# LightSwitch4.net
KiCad netlist of a schematic drawn in EAGLE
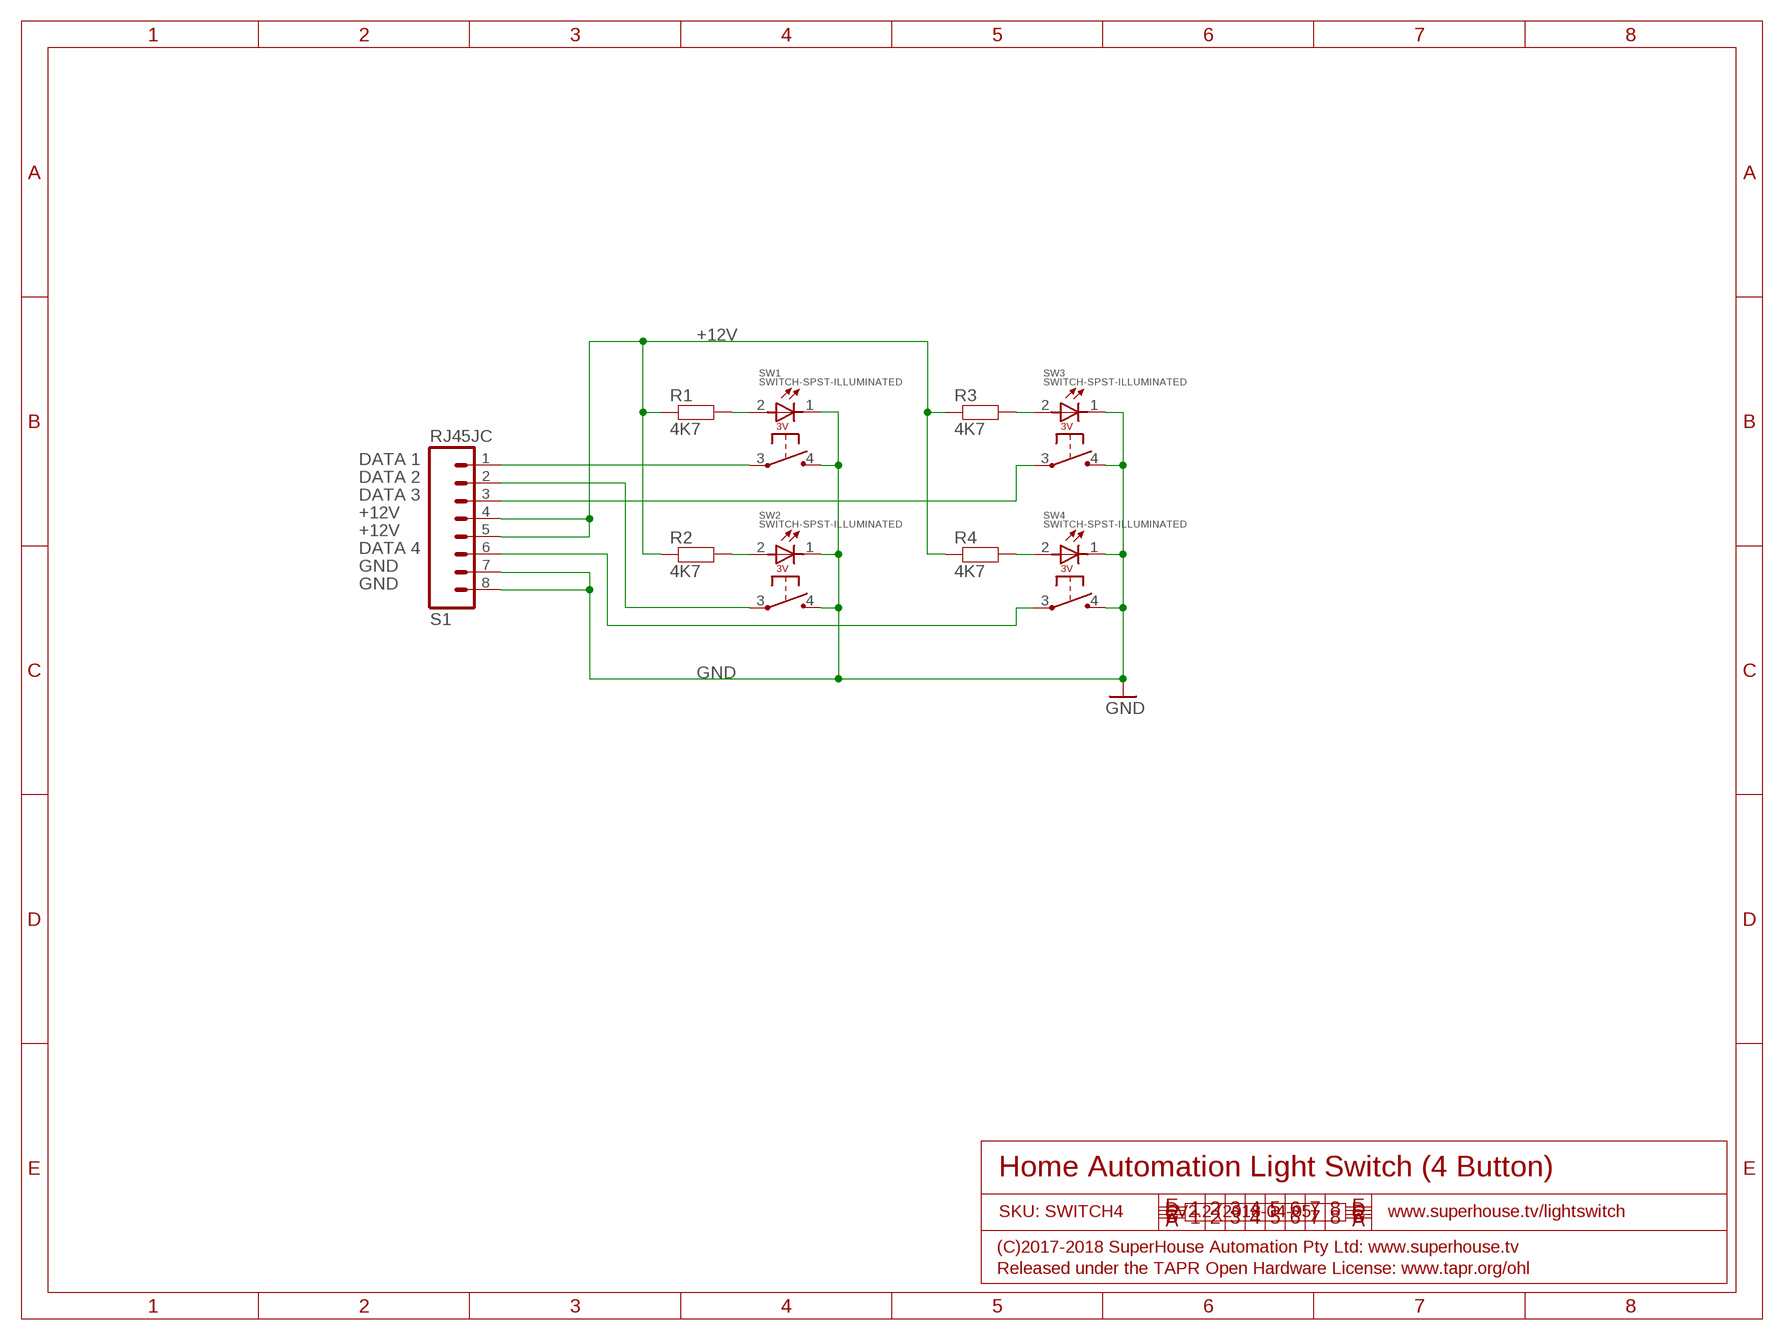
[diagram p0: schematic, sheet 1]

(export (version "E")
  (design (tool "Eeschema 10.0.6"))
  (components
    (comp (ref "R1")
      (value "4K7")
      (footprint "eagle-import:0603")
      (libsource (lib "eagle-import") (part "RESISTOR0603"))
    )
    (comp (ref "R2")
      (value "4K7")
      (footprint "eagle-import:0603")
      (libsource (lib "eagle-import") (part "RESISTOR0603"))
    )
    (comp (ref "R3")
      (value "4K7")
      (footprint "eagle-import:0603")
      (libsource (lib "eagle-import") (part "RESISTOR0603"))
    )
    (comp (ref "R4")
      (value "4K7")
      (footprint "eagle-import:0603")
      (libsource (lib "eagle-import") (part "RESISTOR0603"))
    )
    (comp (ref "S1")
      (value "RJ45JC")
      (footprint "eagle-import:RJ45")
      (libsource (lib "eagle-import") (part "RJ45JC"))
    )
    (comp (ref "SW1")
      (value "SWITCH-SPST-ILLUMINATED")
      (footprint "eagle-import:SWITCH-SPST-ILLUMINATED")
      (libsource (lib "eagle-import") (part "SWITCH-SPST-ILLUMINATED"))
    )
    (comp (ref "SW2")
      (value "SWITCH-SPST-ILLUMINATED")
      (footprint "eagle-import:SWITCH-SPST-ILLUMINATED")
      (libsource (lib "eagle-import") (part "SWITCH-SPST-ILLUMINATED"))
    )
    (comp (ref "SW3")
      (value "SWITCH-SPST-ILLUMINATED")
      (footprint "eagle-import:SWITCH-SPST-ILLUMINATED")
      (libsource (lib "eagle-import") (part "SWITCH-SPST-ILLUMINATED"))
    )
    (comp (ref "SW4")
      (value "SWITCH-SPST-ILLUMINATED")
      (footprint "eagle-import:SWITCH-SPST-ILLUMINATED")
      (libsource (lib "eagle-import") (part "SWITCH-SPST-ILLUMINATED"))
    )
  )
  (nets
    (net (code "1") (name "/+12V") (class "Default")
      (node (ref "R1") (pin "1") (pinfunction "1_1") (pintype "passive"))
      (node (ref "R2") (pin "1") (pinfunction "1_1") (pintype "passive"))
      (node (ref "R3") (pin "1") (pinfunction "1_1") (pintype "passive"))
      (node (ref "R4") (pin "1") (pinfunction "1_1") (pintype "passive"))
      (node (ref "S1") (pin "4") (pinfunction "4_4") (pintype "passive"))
      (node (ref "S1") (pin "5") (pinfunction "5_5") (pintype "passive"))
    )
    (net (code "2") (name "GND") (class "Default")
      (node (ref "S1") (pin "7") (pinfunction "7_7") (pintype "passive"))
      (node (ref "S1") (pin "8") (pinfunction "8_8") (pintype "passive"))
      (node (ref "SW1") (pin "1") (pinfunction "-_1") (pintype "passive"))
      (node (ref "SW1") (pin "4") (pinfunction "NO_4") (pintype "passive"))
      (node (ref "SW2") (pin "1") (pinfunction "-_1") (pintype "passive"))
      (node (ref "SW2") (pin "4") (pinfunction "NO_4") (pintype "passive"))
      (node (ref "SW3") (pin "1") (pinfunction "-_1") (pintype "passive"))
      (node (ref "SW3") (pin "4") (pinfunction "NO_4") (pintype "passive"))
      (node (ref "SW4") (pin "1") (pinfunction "-_1") (pintype "passive"))
      (node (ref "SW4") (pin "4") (pinfunction "NO_4") (pintype "passive"))
    )
    (net (code "3") (name "Net-(SW1-+)") (class "Default")
      (node (ref "R1") (pin "2") (pinfunction "2_2") (pintype "passive"))
      (node (ref "SW1") (pin "2") (pinfunction "+_2") (pintype "passive"))
    )
    (net (code "4") (name "Net-(SW1-COM)") (class "Default")
      (node (ref "S1") (pin "1") (pinfunction "1_1") (pintype "passive"))
      (node (ref "SW1") (pin "3") (pinfunction "COM_3") (pintype "passive"))
    )
    (net (code "5") (name "Net-(SW2-+)") (class "Default")
      (node (ref "R2") (pin "2") (pinfunction "2_2") (pintype "passive"))
      (node (ref "SW2") (pin "2") (pinfunction "+_2") (pintype "passive"))
    )
    (net (code "6") (name "Net-(SW2-COM)") (class "Default")
      (node (ref "S1") (pin "2") (pinfunction "2_2") (pintype "passive"))
      (node (ref "SW2") (pin "3") (pinfunction "COM_3") (pintype "passive"))
    )
    (net (code "7") (name "Net-(SW3-+)") (class "Default")
      (node (ref "R3") (pin "2") (pinfunction "2_2") (pintype "passive"))
      (node (ref "SW3") (pin "2") (pinfunction "+_2") (pintype "passive"))
    )
    (net (code "8") (name "Net-(SW3-COM)") (class "Default")
      (node (ref "S1") (pin "3") (pinfunction "3_3") (pintype "passive"))
      (node (ref "SW3") (pin "3") (pinfunction "COM_3") (pintype "passive"))
    )
    (net (code "9") (name "Net-(SW4-+)") (class "Default")
      (node (ref "R4") (pin "2") (pinfunction "2_2") (pintype "passive"))
      (node (ref "SW4") (pin "2") (pinfunction "+_2") (pintype "passive"))
    )
    (net (code "10") (name "Net-(SW4-COM)") (class "Default")
      (node (ref "S1") (pin "6") (pinfunction "6_6") (pintype "passive"))
      (node (ref "SW4") (pin "3") (pinfunction "COM_3") (pintype "passive"))
    )
  )
)
